# RotaryEncoder.net
KiCad netlist of a schematic drawn in EAGLE
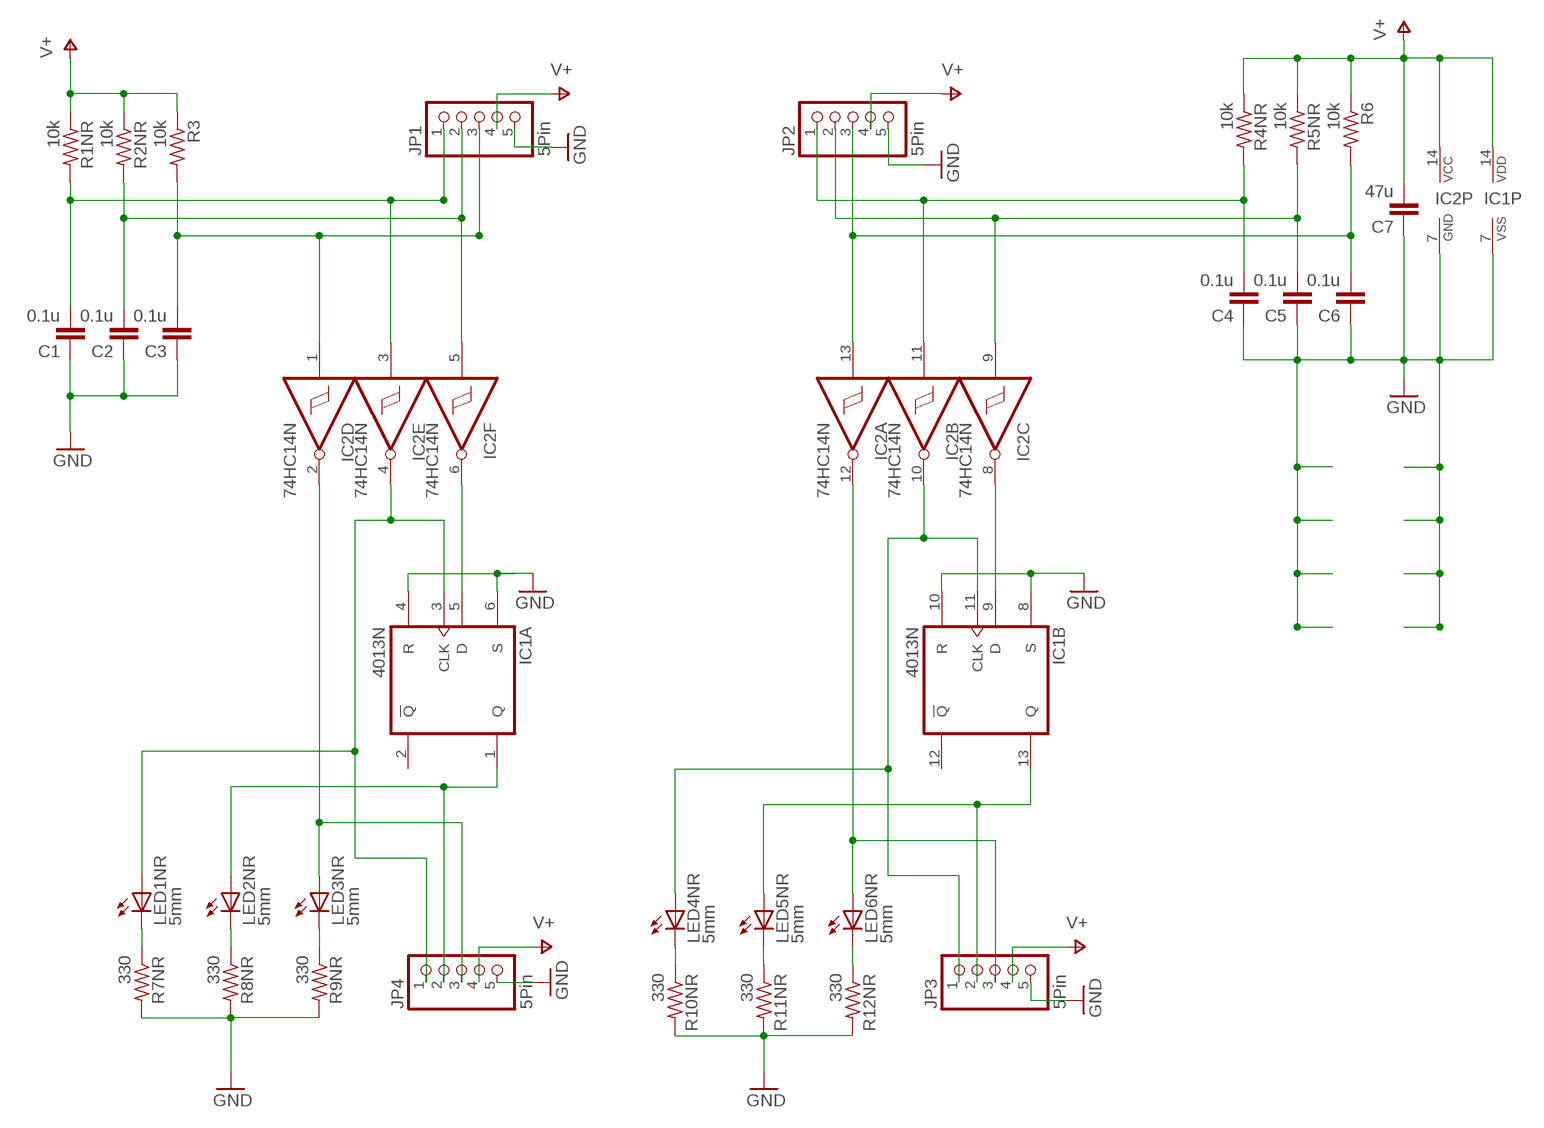
[diagram p0: schematic, sheet 1]

(export (version "E")
  (design (tool "Eeschema 10.0.6"))
  (components
    (comp (ref "C1")
      (value "0.1u")
      (footprint "eagle-import:C7.5B3")
      (libsource (lib "eagle-import") (part "C7.5/3"))
    )
    (comp (ref "C2")
      (value "0.1u")
      (footprint "eagle-import:C7.5B3")
      (libsource (lib "eagle-import") (part "C7.5/3"))
    )
    (comp (ref "C3")
      (value "0.1u")
      (footprint "eagle-import:C7.5B3")
      (libsource (lib "eagle-import") (part "C7.5/3"))
    )
    (comp (ref "C4")
      (value "0.1u")
      (footprint "eagle-import:C7.5B3")
      (libsource (lib "eagle-import") (part "C7.5/3"))
    )
    (comp (ref "C5")
      (value "0.1u")
      (footprint "eagle-import:C7.5B3")
      (libsource (lib "eagle-import") (part "C7.5/3"))
    )
    (comp (ref "C6")
      (value "0.1u")
      (footprint "eagle-import:C7.5B3")
      (libsource (lib "eagle-import") (part "C7.5/3"))
    )
    (comp (ref "C7")
      (value "47u")
      (footprint "eagle-import:C7.5B3")
      (libsource (lib "eagle-import") (part "C7.5/3"))
    )
    (comp (ref "IC1")
      (value "4013N")
      (footprint "eagle-import:DIL14")
      (libsource (lib "eagle-import") (part "4013N"))
    )
    (comp (ref "IC2")
      (value "74HC14N")
      (footprint "eagle-import:DIL14")
      (libsource (lib "eagle-import") (part "7414NHC"))
    )
    (comp (ref "JP1")
      (value "5Pin")
      (footprint "eagle-import:1X05")
      (libsource (lib "eagle-import") (part "PINHD-1X5"))
    )
    (comp (ref "JP2")
      (value "5Pin")
      (footprint "eagle-import:1X05")
      (libsource (lib "eagle-import") (part "PINHD-1X5"))
    )
    (comp (ref "JP3")
      (value "5Pin")
      (footprint "eagle-import:1X05")
      (libsource (lib "eagle-import") (part "PINHD-1X5"))
    )
    (comp (ref "JP4")
      (value "5Pin")
      (footprint "eagle-import:1X05")
      (libsource (lib "eagle-import") (part "PINHD-1X5"))
    )
    (comp (ref "LED1NR")
      (value "5mm")
      (footprint "eagle-import:LED5MM")
      (libsource (lib "eagle-import") (part "LED5MM"))
    )
    (comp (ref "LED2NR")
      (value "5mm")
      (footprint "eagle-import:LED5MM")
      (libsource (lib "eagle-import") (part "LED5MM"))
    )
    (comp (ref "LED3NR")
      (value "5mm")
      (footprint "eagle-import:LED5MM")
      (libsource (lib "eagle-import") (part "LED5MM"))
    )
    (comp (ref "LED4NR")
      (value "5mm")
      (footprint "eagle-import:LED5MM")
      (libsource (lib "eagle-import") (part "LED5MM"))
    )
    (comp (ref "LED5NR")
      (value "5mm")
      (footprint "eagle-import:LED5MM")
      (libsource (lib "eagle-import") (part "LED5MM"))
    )
    (comp (ref "LED6NR")
      (value "5mm")
      (footprint "eagle-import:LED5MM")
      (libsource (lib "eagle-import") (part "LED5MM"))
    )
    (comp (ref "R1NR")
      (value "10k")
      (footprint "eagle-import:0411_15")
      (libsource (lib "eagle-import") (part "R-US_0411/15"))
    )
    (comp (ref "R2NR")
      (value "10k")
      (footprint "eagle-import:0411_15")
      (libsource (lib "eagle-import") (part "R-US_0411/15"))
    )
    (comp (ref "R3")
      (value "10k")
      (footprint "eagle-import:0411_15")
      (libsource (lib "eagle-import") (part "R-US_0411/15"))
    )
    (comp (ref "R4NR")
      (value "10k")
      (footprint "eagle-import:0411_15")
      (libsource (lib "eagle-import") (part "R-US_0411/15"))
    )
    (comp (ref "R5NR")
      (value "10k")
      (footprint "eagle-import:0411_15")
      (libsource (lib "eagle-import") (part "R-US_0411/15"))
    )
    (comp (ref "R6")
      (value "10k")
      (footprint "eagle-import:0411_15")
      (libsource (lib "eagle-import") (part "R-US_0411/15"))
    )
    (comp (ref "R7NR")
      (value "330")
      (footprint "eagle-import:0411_15")
      (libsource (lib "eagle-import") (part "R-US_0411/15"))
    )
    (comp (ref "R8NR")
      (value "330")
      (footprint "eagle-import:0411_15")
      (libsource (lib "eagle-import") (part "R-US_0411/15"))
    )
    (comp (ref "R9NR")
      (value "330")
      (footprint "eagle-import:0411_15")
      (libsource (lib "eagle-import") (part "R-US_0411/15"))
    )
    (comp (ref "R10NR")
      (value "330")
      (footprint "eagle-import:0411_15")
      (libsource (lib "eagle-import") (part "R-US_0411/15"))
    )
    (comp (ref "R11NR")
      (value "330")
      (footprint "eagle-import:0411_15")
      (libsource (lib "eagle-import") (part "R-US_0411/15"))
    )
    (comp (ref "R12NR")
      (value "330")
      (footprint "eagle-import:0411_15")
      (libsource (lib "eagle-import") (part "R-US_0411/15"))
    )
  )
  (nets
    (net (code "1") (name "GND") (class "Default")
      (node (ref "C1") (pin "1") (pinfunction "1_1") (pintype "passive"))
      (node (ref "C2") (pin "1") (pinfunction "1_1") (pintype "passive"))
      (node (ref "C3") (pin "1") (pinfunction "1_1") (pintype "passive"))
      (node (ref "C4") (pin "1") (pinfunction "1_1") (pintype "passive"))
      (node (ref "C5") (pin "1") (pinfunction "1_1") (pintype "passive"))
      (node (ref "C6") (pin "1") (pinfunction "1_1") (pintype "passive"))
      (node (ref "C7") (pin "1") (pinfunction "1_1") (pintype "passive"))
      (node (ref "IC1") (pin "10") (pinfunction "R_10") (pintype "input"))
      (node (ref "IC1") (pin "4") (pinfunction "R_4") (pintype "input"))
      (node (ref "IC1") (pin "6") (pinfunction "S_6") (pintype "input"))
      (node (ref "IC1") (pin "7") (pinfunction "VSS_7") (pintype "power_in"))
      (node (ref "IC1") (pin "8") (pinfunction "S_8") (pintype "input"))
      (node (ref "IC2") (pin "7") (pinfunction "GND_7") (pintype "power_in"))
      (node (ref "JP1") (pin "5") (pinfunction "5_5") (pintype "passive"))
      (node (ref "JP2") (pin "5") (pinfunction "5_5") (pintype "passive"))
      (node (ref "JP3") (pin "5") (pinfunction "5_5") (pintype "passive"))
      (node (ref "JP4") (pin "5") (pinfunction "5_5") (pintype "passive"))
      (node (ref "R10NR") (pin "2") (pinfunction "2_2") (pintype "passive"))
      (node (ref "R11NR") (pin "2") (pinfunction "2_2") (pintype "passive"))
      (node (ref "R12NR") (pin "2") (pinfunction "2_2") (pintype "passive"))
      (node (ref "R7NR") (pin "2") (pinfunction "2_2") (pintype "passive"))
      (node (ref "R8NR") (pin "2") (pinfunction "2_2") (pintype "passive"))
      (node (ref "R9NR") (pin "2") (pinfunction "2_2") (pintype "passive"))
    )
    (net (code "2") (name "Net-(IC1A-CLK)") (class "Default")
      (node (ref "IC1") (pin "3") (pinfunction "CLK_3") (pintype "input"))
      (node (ref "IC2") (pin "4") (pinfunction "O_4") (pintype "output"))
      (node (ref "JP4") (pin "1") (pinfunction "1_1") (pintype "passive"))
      (node (ref "LED1NR") (pin "A") (pinfunction "A_A") (pintype "passive"))
    )
    (net (code "3") (name "Net-(IC1A-D)") (class "Default")
      (node (ref "IC1") (pin "5") (pinfunction "D_5") (pintype "input"))
      (node (ref "IC2") (pin "6") (pinfunction "O_6") (pintype "output"))
    )
    (net (code "4") (name "Net-(IC1A-Q)") (class "Default")
      (node (ref "IC1") (pin "1") (pinfunction "Q_1") (pintype "output"))
      (node (ref "JP4") (pin "2") (pinfunction "2_2") (pintype "passive"))
      (node (ref "LED2NR") (pin "A") (pinfunction "A_A") (pintype "passive"))
    )
    (net (code "5") (name "Net-(IC1B-CLK)") (class "Default")
      (node (ref "IC1") (pin "11") (pinfunction "CLK_11") (pintype "input"))
      (node (ref "IC2") (pin "10") (pinfunction "O_10") (pintype "output"))
      (node (ref "JP3") (pin "1") (pinfunction "1_1") (pintype "passive"))
      (node (ref "LED4NR") (pin "A") (pinfunction "A_A") (pintype "passive"))
    )
    (net (code "6") (name "Net-(IC1B-D)") (class "Default")
      (node (ref "IC1") (pin "9") (pinfunction "D_9") (pintype "input"))
      (node (ref "IC2") (pin "8") (pinfunction "O_8") (pintype "output"))
    )
    (net (code "7") (name "Net-(IC1B-Q)") (class "Default")
      (node (ref "IC1") (pin "13") (pinfunction "Q_13") (pintype "output"))
      (node (ref "JP3") (pin "2") (pinfunction "2_2") (pintype "passive"))
      (node (ref "LED5NR") (pin "A") (pinfunction "A_A") (pintype "passive"))
    )
    (net (code "8") (name "Net-(IC2A-I)") (class "Default")
      (node (ref "C6") (pin "2") (pinfunction "2_2") (pintype "passive"))
      (node (ref "IC2") (pin "13") (pinfunction "I_13") (pintype "input"))
      (node (ref "JP2") (pin "3") (pinfunction "3_3") (pintype "passive"))
      (node (ref "R6") (pin "2") (pinfunction "2_2") (pintype "passive"))
    )
    (net (code "9") (name "Net-(IC2A-O)") (class "Default")
      (node (ref "IC2") (pin "12") (pinfunction "O_12") (pintype "output"))
      (node (ref "JP3") (pin "3") (pinfunction "3_3") (pintype "passive"))
      (node (ref "LED6NR") (pin "A") (pinfunction "A_A") (pintype "passive"))
    )
    (net (code "10") (name "Net-(IC2B-I)") (class "Default")
      (node (ref "C4") (pin "2") (pinfunction "2_2") (pintype "passive"))
      (node (ref "IC2") (pin "11") (pinfunction "I_11") (pintype "input"))
      (node (ref "JP2") (pin "1") (pinfunction "1_1") (pintype "passive"))
      (node (ref "R4NR") (pin "2") (pinfunction "2_2") (pintype "passive"))
    )
    (net (code "11") (name "Net-(IC2C-I)") (class "Default")
      (node (ref "C5") (pin "2") (pinfunction "2_2") (pintype "passive"))
      (node (ref "IC2") (pin "9") (pinfunction "I_9") (pintype "input"))
      (node (ref "JP2") (pin "2") (pinfunction "2_2") (pintype "passive"))
      (node (ref "R5NR") (pin "2") (pinfunction "2_2") (pintype "passive"))
    )
    (net (code "12") (name "Net-(IC2D-I)") (class "Default")
      (node (ref "C3") (pin "2") (pinfunction "2_2") (pintype "passive"))
      (node (ref "IC2") (pin "1") (pinfunction "I_1") (pintype "input"))
      (node (ref "JP1") (pin "3") (pinfunction "3_3") (pintype "passive"))
      (node (ref "R3") (pin "2") (pinfunction "2_2") (pintype "passive"))
    )
    (net (code "13") (name "Net-(IC2D-O)") (class "Default")
      (node (ref "IC2") (pin "2") (pinfunction "O_2") (pintype "output"))
      (node (ref "JP4") (pin "3") (pinfunction "3_3") (pintype "passive"))
      (node (ref "LED3NR") (pin "A") (pinfunction "A_A") (pintype "passive"))
    )
    (net (code "14") (name "Net-(IC2E-I)") (class "Default")
      (node (ref "C1") (pin "2") (pinfunction "2_2") (pintype "passive"))
      (node (ref "IC2") (pin "3") (pinfunction "I_3") (pintype "input"))
      (node (ref "JP1") (pin "1") (pinfunction "1_1") (pintype "passive"))
      (node (ref "R1NR") (pin "2") (pinfunction "2_2") (pintype "passive"))
    )
    (net (code "15") (name "Net-(IC2F-I)") (class "Default")
      (node (ref "C2") (pin "2") (pinfunction "2_2") (pintype "passive"))
      (node (ref "IC2") (pin "5") (pinfunction "I_5") (pintype "input"))
      (node (ref "JP1") (pin "2") (pinfunction "2_2") (pintype "passive"))
      (node (ref "R2NR") (pin "2") (pinfunction "2_2") (pintype "passive"))
    )
    (net (code "16") (name "Net-(LED1NR-C)") (class "Default")
      (node (ref "LED1NR") (pin "K") (pinfunction "C_K") (pintype "passive"))
      (node (ref "R7NR") (pin "1") (pinfunction "1_1") (pintype "passive"))
    )
    (net (code "17") (name "Net-(LED2NR-C)") (class "Default")
      (node (ref "LED2NR") (pin "K") (pinfunction "C_K") (pintype "passive"))
      (node (ref "R8NR") (pin "1") (pinfunction "1_1") (pintype "passive"))
    )
    (net (code "18") (name "Net-(LED3NR-C)") (class "Default")
      (node (ref "LED3NR") (pin "K") (pinfunction "C_K") (pintype "passive"))
      (node (ref "R9NR") (pin "1") (pinfunction "1_1") (pintype "passive"))
    )
    (net (code "19") (name "Net-(LED4NR-C)") (class "Default")
      (node (ref "LED4NR") (pin "K") (pinfunction "C_K") (pintype "passive"))
      (node (ref "R10NR") (pin "1") (pinfunction "1_1") (pintype "passive"))
    )
    (net (code "20") (name "Net-(LED5NR-C)") (class "Default")
      (node (ref "LED5NR") (pin "K") (pinfunction "C_K") (pintype "passive"))
      (node (ref "R11NR") (pin "1") (pinfunction "1_1") (pintype "passive"))
    )
    (net (code "21") (name "Net-(LED6NR-C)") (class "Default")
      (node (ref "LED6NR") (pin "K") (pinfunction "C_K") (pintype "passive"))
      (node (ref "R12NR") (pin "1") (pinfunction "1_1") (pintype "passive"))
    )
    (net (code "22") (name "V+") (class "Default")
      (node (ref "C7") (pin "2") (pinfunction "2_2") (pintype "passive"))
      (node (ref "IC1") (pin "14") (pinfunction "VDD_14") (pintype "power_in"))
      (node (ref "IC2") (pin "14") (pinfunction "VCC_14") (pintype "power_in"))
      (node (ref "JP1") (pin "4") (pinfunction "4_4") (pintype "passive"))
      (node (ref "JP2") (pin "4") (pinfunction "4_4") (pintype "passive"))
      (node (ref "JP3") (pin "4") (pinfunction "4_4") (pintype "passive"))
      (node (ref "JP4") (pin "4") (pinfunction "4_4") (pintype "passive"))
      (node (ref "R1NR") (pin "1") (pinfunction "1_1") (pintype "passive"))
      (node (ref "R2NR") (pin "1") (pinfunction "1_1") (pintype "passive"))
      (node (ref "R3") (pin "1") (pinfunction "1_1") (pintype "passive"))
      (node (ref "R4NR") (pin "1") (pinfunction "1_1") (pintype "passive"))
      (node (ref "R5NR") (pin "1") (pinfunction "1_1") (pintype "passive"))
      (node (ref "R6") (pin "1") (pinfunction "1_1") (pintype "passive"))
    )
    (net (code "23") (name "unconnected-(IC1A-~{Q}-Pad2)") (class "Default")
      (node (ref "IC1") (pin "2") (pinfunction "~{Q}_2") (pintype "output"))
    )
    (net (code "24") (name "unconnected-(IC1B-~{Q}-Pad12)") (class "Default")
      (node (ref "IC1") (pin "12") (pinfunction "~{Q}_12") (pintype "output"))
    )
  )
)
